# Power_USB.net
KiCad netlist of a schematic drawn in Altium Designer
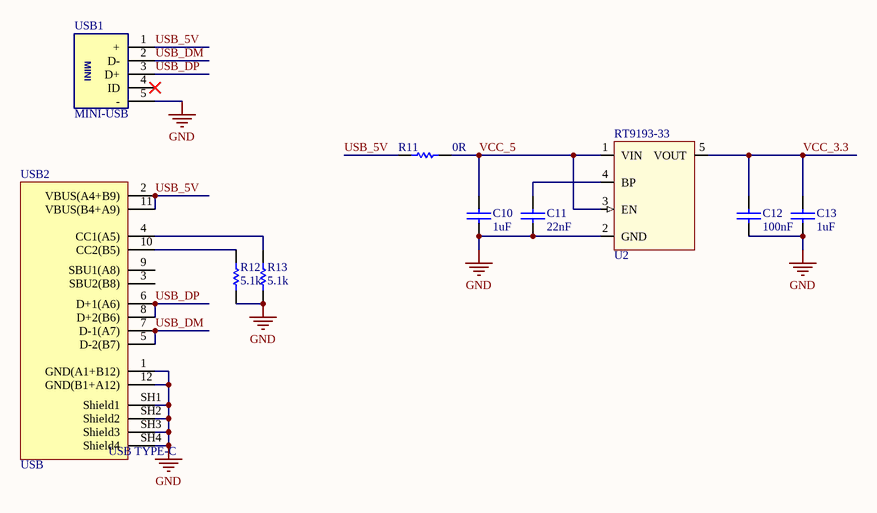
[diagram p0: Power_USB.SchDoc]

(export (version "E")
  (design (tool "Eeschema 10.0.6"))
  (components
    (comp (ref "C10")
      (value "1uF")
      (footprint "C 0603_L")
      (description "无极性电容")
      (libsource (lib "电容") (part "CAP"))
    )
    (comp (ref "C11")
      (value "22nF")
      (footprint "C 0603_L")
      (description "无极性电容")
      (libsource (lib "电容") (part "CAP"))
    )
    (comp (ref "C12")
      (value "100nF")
      (footprint "C 0603_L")
      (description "无极性电容")
      (libsource (lib "电容") (part "CAP"))
    )
    (comp (ref "C13")
      (value "1uF")
      (footprint "C 0603_L")
      (description "无极性电容")
      (libsource (lib "电容") (part "CAP"))
    )
    (comp (ref "R11") (value "0R") (footprint "0603R") (libsource (lib "电阻") (part "RES")))
    (comp (ref "R12") (value "5.1k") (footprint "0603R") (libsource (lib "电阻") (part "RES")))
    (comp (ref "R13") (value "5.1k") (footprint "0603R") (libsource (lib "电阻") (part "RES")))
    (comp (ref "U2")
      (value "RT9193-33")
      (fields (field (name "ICA_PARTNUM") "$$2191094$$RT9193-15CU5") (field (name "PART NUMBER") "TMP-13"))
      (libsource (lib "SchLib1") (part "RT9193X_5P"))
    )
    (comp (ref "USB1") (value "MINI-USB") (footprint "USB-MINI-A") (libsource (lib "USB") (part "MINI-USB")))
    (comp (ref "USB2")
      (value "USB")
      (footprint "USB Type-C")
      (description "12P TypeC 母座")
      (libsource (lib "DNF429P_F767P_H743P V2.4") (part "USB Type-C"))
    )
  )
  (nets
    (net (code "1") (name "/USB_5V") (class "Default")
      (node (ref "R11") (pin "1") (pinfunction "1_1") (pintype "passive"))
      (node (ref "USB1") (pin "1") (pinfunction "+_1") (pintype "passive"))
      (node (ref "USB2") (pin "11") (pinfunction "VBUS(B4+A9)_11") (pintype "passive"))
      (node (ref "USB2") (pin "2") (pinfunction "VBUS(A4+B9)_2") (pintype "passive"))
    )
    (net (code "2") (name "/USB_DM") (class "Default")
      (node (ref "USB1") (pin "2") (pinfunction "D-_2") (pintype "passive"))
      (node (ref "USB2") (pin "5") (pinfunction "D-2(B7)_5") (pintype "passive"))
      (node (ref "USB2") (pin "7") (pinfunction "D-1(A7)_7") (pintype "passive"))
    )
    (net (code "3") (name "/USB_DP") (class "Default")
      (node (ref "USB1") (pin "3") (pinfunction "D+_3") (pintype "passive"))
      (node (ref "USB2") (pin "6") (pinfunction "D+1(A6)_6") (pintype "passive"))
      (node (ref "USB2") (pin "8") (pinfunction "D+2(B6)_8") (pintype "passive"))
    )
    (net (code "4") (name "/VCC_3.3") (class "Default")
      (node (ref "C12") (pin "2") (pinfunction "2_2") (pintype "passive"))
      (node (ref "C13") (pin "2") (pinfunction "2_2") (pintype "passive"))
      (node (ref "U2") (pin "5") (pinfunction "VOUT_5") (pintype "power_in"))
    )
    (net (code "5") (name "/VCC_5") (class "Default")
      (node (ref "C10") (pin "2") (pinfunction "2_2") (pintype "passive"))
      (node (ref "R11") (pin "2") (pinfunction "2_2") (pintype "passive"))
      (node (ref "U2") (pin "1") (pinfunction "VIN_1") (pintype "power_in"))
      (node (ref "U2") (pin "3") (pinfunction "EN_3") (pintype "input"))
    )
    (net (code "6") (name "GND") (class "Default")
      (node (ref "C10") (pin "1") (pinfunction "1_1") (pintype "passive"))
      (node (ref "C11") (pin "1") (pinfunction "1_1") (pintype "passive"))
      (node (ref "C12") (pin "1") (pinfunction "1_1") (pintype "passive"))
      (node (ref "C13") (pin "1") (pinfunction "1_1") (pintype "passive"))
      (node (ref "R12") (pin "2") (pinfunction "2_2") (pintype "passive"))
      (node (ref "R13") (pin "2") (pinfunction "2_2") (pintype "passive"))
      (node (ref "U2") (pin "2") (pinfunction "GND_2") (pintype "power_in"))
      (node (ref "USB1") (pin "5") (pinfunction "-_5") (pintype "passive"))
      (node (ref "USB2") (pin "1") (pinfunction "GND(A1+B12)_1") (pintype "passive"))
      (node (ref "USB2") (pin "12") (pinfunction "GND(B1+A12)_12") (pintype "passive"))
      (node (ref "USB2") (pin "SH1") (pinfunction "Shield1_SH1") (pintype "passive"))
      (node (ref "USB2") (pin "SH2") (pinfunction "Shield2_SH2") (pintype "passive"))
      (node (ref "USB2") (pin "SH3") (pinfunction "Shield3_SH3") (pintype "passive"))
      (node (ref "USB2") (pin "SH4") (pinfunction "Shield4_SH4") (pintype "passive"))
    )
    (net (code "7") (name "Net-(U2-BP)") (class "Default")
      (node (ref "C11") (pin "2") (pinfunction "2_2") (pintype "passive"))
      (node (ref "U2") (pin "4") (pinfunction "BP_4") (pintype "passive"))
    )
    (net (code "8") (name "Net-(USB2-CC1(A5))") (class "Default")
      (node (ref "R13") (pin "1") (pinfunction "1_1") (pintype "passive"))
      (node (ref "USB2") (pin "4") (pinfunction "CC1(A5)_4") (pintype "passive"))
    )
    (net (code "9") (name "Net-(USB2-CC2(B5))") (class "Default")
      (node (ref "R12") (pin "1") (pinfunction "1_1") (pintype "passive"))
      (node (ref "USB2") (pin "10") (pinfunction "CC2(B5)_10") (pintype "passive"))
    )
    (net (code "10") (name "unconnected-(USB1-ID-Pad4)") (class "Default")
      (node (ref "USB1") (pin "4") (pinfunction "ID_4") (pintype "passive+no_connect"))
    )
    (net (code "11") (name "unconnected-(USB2-SBU1(A8)-Pad9)") (class "Default")
      (node (ref "USB2") (pin "9") (pinfunction "SBU1(A8)_9") (pintype "passive"))
    )
    (net (code "12") (name "unconnected-(USB2-SBU2(B8)-Pad3)") (class "Default")
      (node (ref "USB2") (pin "3") (pinfunction "SBU2(B8)_3") (pintype "passive"))
    )
  )
)
